# LCs.net
KiCad netlist of a schematic drawn in Altium Designer
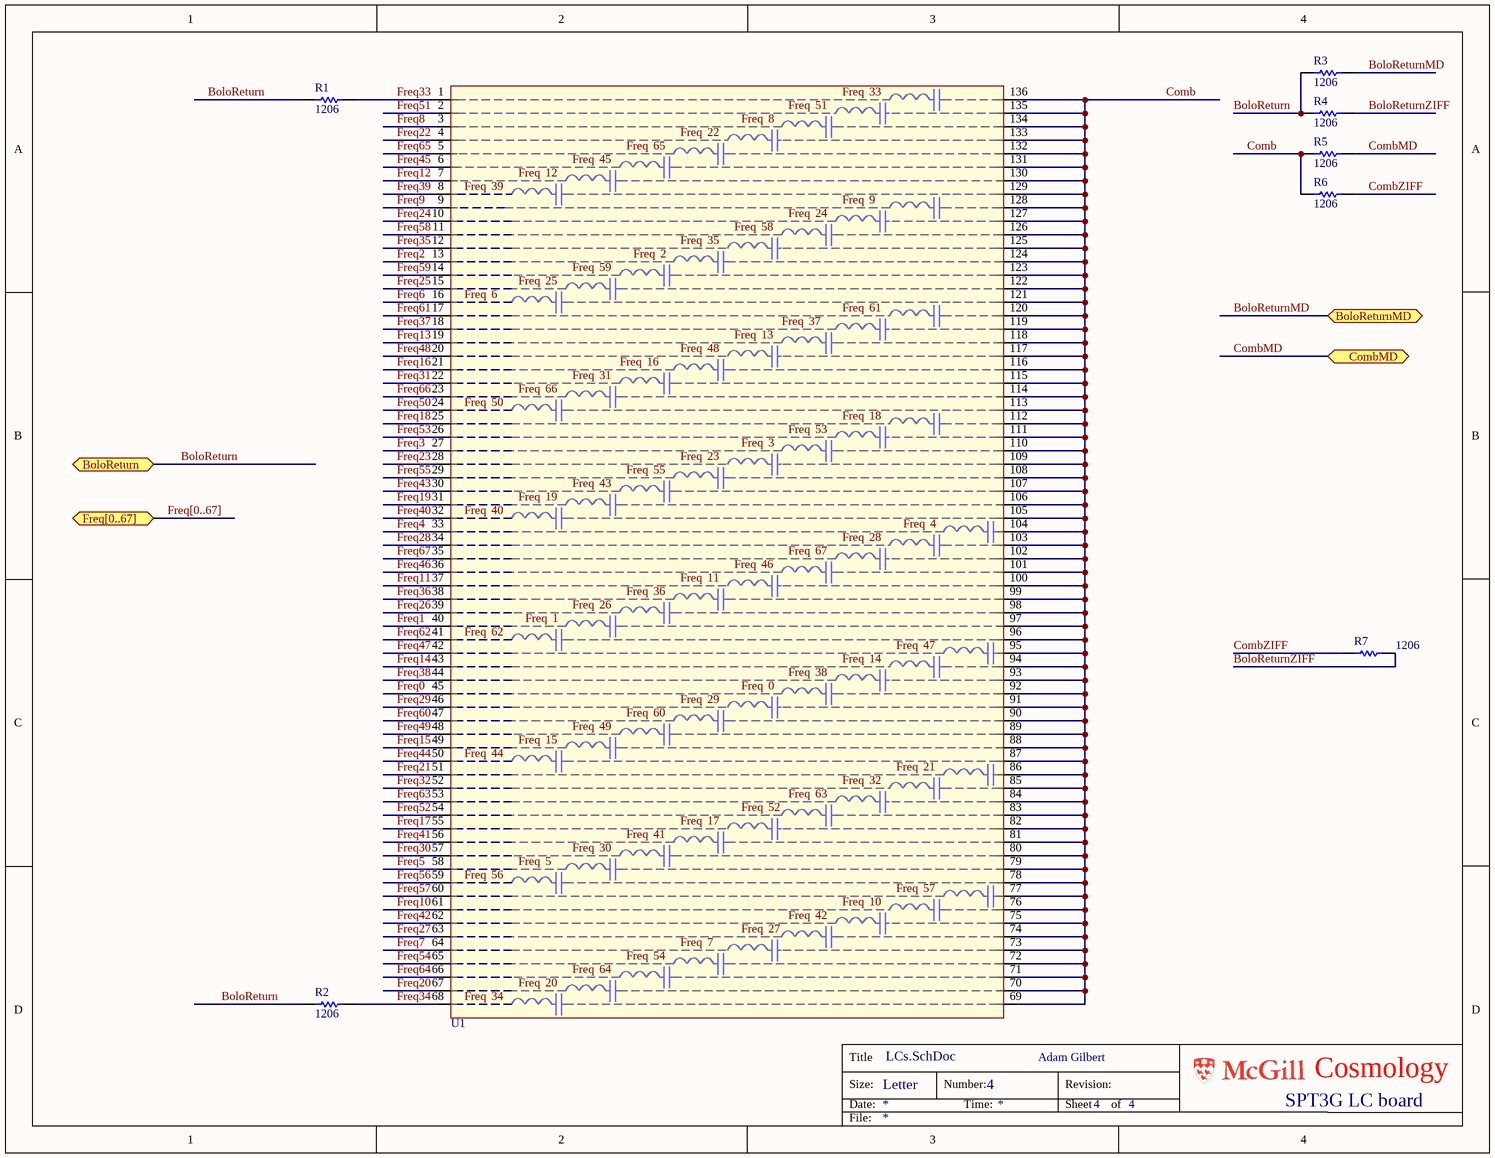
[diagram p0: LCs.SchDoc]

(export (version "E")
  (design (tool "Eeschema 10.0.6"))
  (components
    (comp (ref "R1")
      (value "Res1206")
      (footprint "1206")
      (description "Resistor")
      (libsource (lib "SPT3G_LCBoard") (part "Res1206"))
    )
    (comp (ref "R2")
      (value "Res1206")
      (footprint "1206")
      (description "Resistor")
      (libsource (lib "SPT3G_LCBoard") (part "Res1206"))
    )
    (comp (ref "R3")
      (value "Res1206")
      (footprint "1206")
      (description "Resistor")
      (libsource (lib "SPT3G_LCBoard") (part "Res1206"))
    )
    (comp (ref "R4")
      (value "Res1206")
      (footprint "1206")
      (description "Resistor")
      (libsource (lib "SPT3G_LCBoard") (part "Res1206"))
    )
    (comp (ref "R5")
      (value "Res1206")
      (footprint "1206")
      (description "Resistor")
      (libsource (lib "SPT3G_LCBoard") (part "Res1206"))
    )
    (comp (ref "R6")
      (value "Res1206")
      (footprint "1206")
      (description "Resistor")
      (libsource (lib "SPT3G_LCBoard") (part "Res1206"))
    )
    (comp (ref "R7")
      (value "Res1206")
      (footprint "1206")
      (description "Resistor")
      (libsource (lib "SPT3G_LCBoard") (part "Res1206"))
    )
    (comp (ref "U1")
      (value "LC68_wafer")
      (footprint "68xLC")
      (description "Gold bonded integrated LC")
      (libsource (lib "SPT3G_LCBoard") (part "LC68Wafer"))
    )
  )
  (nets
    (net (code "1") (name "/BoloReturn") (class "Default")
      (node (ref "R1") (pin "1") (pinfunction "1_1") (pintype "passive"))
      (node (ref "R2") (pin "1") (pinfunction "1_1") (pintype "passive"))
      (node (ref "R3") (pin "1") (pinfunction "1_1") (pintype "passive"))
      (node (ref "R4") (pin "1") (pinfunction "1_1") (pintype "passive"))
    )
    (net (code "2") (name "/BoloReturnMD") (class "Default")
      (node (ref "R3") (pin "2") (pinfunction "2_2") (pintype "passive"))
    )
    (net (code "3") (name "/BoloReturnZIFF") (class "Default")
      (node (ref "R4") (pin "2") (pinfunction "2_2") (pintype "passive"))
      (node (ref "R7") (pin "1") (pinfunction "1_1") (pintype "passive"))
    )
    (net (code "4") (name "/Comb") (class "Default")
      (node (ref "R5") (pin "1") (pinfunction "1_1") (pintype "passive"))
      (node (ref "R6") (pin "1") (pinfunction "1_1") (pintype "passive"))
      (node (ref "U1") (pin "100") (pinfunction "100_100") (pintype "passive"))
      (node (ref "U1") (pin "101") (pinfunction "101_101") (pintype "passive"))
      (node (ref "U1") (pin "102") (pinfunction "102_102") (pintype "passive"))
      (node (ref "U1") (pin "103") (pinfunction "103_103") (pintype "passive"))
      (node (ref "U1") (pin "104") (pinfunction "104_104") (pintype "passive"))
      (node (ref "U1") (pin "105") (pinfunction "105_105") (pintype "passive"))
      (node (ref "U1") (pin "106") (pinfunction "106_106") (pintype "passive"))
      (node (ref "U1") (pin "107") (pinfunction "107_107") (pintype "passive"))
      (node (ref "U1") (pin "108") (pinfunction "108_108") (pintype "passive"))
      (node (ref "U1") (pin "109") (pinfunction "109_109") (pintype "passive"))
      (node (ref "U1") (pin "110") (pinfunction "110_110") (pintype "passive"))
      (node (ref "U1") (pin "111") (pinfunction "111_111") (pintype "passive"))
      (node (ref "U1") (pin "112") (pinfunction "112_112") (pintype "passive"))
      (node (ref "U1") (pin "113") (pinfunction "113_113") (pintype "passive"))
      (node (ref "U1") (pin "114") (pinfunction "114_114") (pintype "passive"))
      (node (ref "U1") (pin "115") (pinfunction "115_115") (pintype "passive"))
      (node (ref "U1") (pin "116") (pinfunction "116_116") (pintype "passive"))
      (node (ref "U1") (pin "117") (pinfunction "117_117") (pintype "passive"))
      (node (ref "U1") (pin "118") (pinfunction "118_118") (pintype "passive"))
      (node (ref "U1") (pin "119") (pinfunction "119_119") (pintype "passive"))
      (node (ref "U1") (pin "120") (pinfunction "120_120") (pintype "passive"))
      (node (ref "U1") (pin "121") (pinfunction "121_121") (pintype "passive"))
      (node (ref "U1") (pin "122") (pinfunction "122_122") (pintype "passive"))
      (node (ref "U1") (pin "123") (pinfunction "123_123") (pintype "passive"))
      (node (ref "U1") (pin "124") (pinfunction "124_124") (pintype "passive"))
      (node (ref "U1") (pin "125") (pinfunction "125_125") (pintype "passive"))
      (node (ref "U1") (pin "126") (pinfunction "126_126") (pintype "passive"))
      (node (ref "U1") (pin "127") (pinfunction "127_127") (pintype "passive"))
      (node (ref "U1") (pin "128") (pinfunction "128_128") (pintype "passive"))
      (node (ref "U1") (pin "129") (pinfunction "129_129") (pintype "passive"))
      (node (ref "U1") (pin "130") (pinfunction "130_130") (pintype "passive"))
      (node (ref "U1") (pin "131") (pinfunction "131_131") (pintype "passive"))
      (node (ref "U1") (pin "132") (pinfunction "132_132") (pintype "passive"))
      (node (ref "U1") (pin "133") (pinfunction "133_133") (pintype "passive"))
      (node (ref "U1") (pin "134") (pinfunction "134_134") (pintype "passive"))
      (node (ref "U1") (pin "135") (pinfunction "135_135") (pintype "passive"))
      (node (ref "U1") (pin "136") (pinfunction "136_136") (pintype "passive"))
      (node (ref "U1") (pin "69") (pinfunction "69_69") (pintype "passive"))
      (node (ref "U1") (pin "70") (pinfunction "70_70") (pintype "passive"))
      (node (ref "U1") (pin "71") (pinfunction "71_71") (pintype "passive"))
      (node (ref "U1") (pin "72") (pinfunction "72_72") (pintype "passive"))
      (node (ref "U1") (pin "73") (pinfunction "73_73") (pintype "passive"))
      (node (ref "U1") (pin "74") (pinfunction "74_74") (pintype "passive"))
      (node (ref "U1") (pin "75") (pinfunction "75_75") (pintype "passive"))
      (node (ref "U1") (pin "76") (pinfunction "76_76") (pintype "passive"))
      (node (ref "U1") (pin "77") (pinfunction "77_77") (pintype "passive"))
      (node (ref "U1") (pin "78") (pinfunction "78_78") (pintype "passive"))
      (node (ref "U1") (pin "79") (pinfunction "79_79") (pintype "passive"))
      (node (ref "U1") (pin "80") (pinfunction "80_80") (pintype "passive"))
      (node (ref "U1") (pin "81") (pinfunction "81_81") (pintype "passive"))
      (node (ref "U1") (pin "82") (pinfunction "82_82") (pintype "passive"))
      (node (ref "U1") (pin "83") (pinfunction "83_83") (pintype "passive"))
      (node (ref "U1") (pin "84") (pinfunction "84_84") (pintype "passive"))
      (node (ref "U1") (pin "85") (pinfunction "85_85") (pintype "passive"))
      (node (ref "U1") (pin "86") (pinfunction "86_86") (pintype "passive"))
      (node (ref "U1") (pin "87") (pinfunction "87_87") (pintype "passive"))
      (node (ref "U1") (pin "88") (pinfunction "88_88") (pintype "passive"))
      (node (ref "U1") (pin "89") (pinfunction "89_89") (pintype "passive"))
      (node (ref "U1") (pin "90") (pinfunction "90_90") (pintype "passive"))
      (node (ref "U1") (pin "91") (pinfunction "91_91") (pintype "passive"))
      (node (ref "U1") (pin "92") (pinfunction "92_92") (pintype "passive"))
      (node (ref "U1") (pin "93") (pinfunction "93_93") (pintype "passive"))
      (node (ref "U1") (pin "94") (pinfunction "94_94") (pintype "passive"))
      (node (ref "U1") (pin "95") (pinfunction "95_95") (pintype "passive"))
      (node (ref "U1") (pin "96") (pinfunction "96_96") (pintype "passive"))
      (node (ref "U1") (pin "97") (pinfunction "97_97") (pintype "passive"))
      (node (ref "U1") (pin "98") (pinfunction "98_98") (pintype "passive"))
      (node (ref "U1") (pin "99") (pinfunction "99_99") (pintype "passive"))
    )
    (net (code "5") (name "/CombMD") (class "Default")
      (node (ref "R5") (pin "2") (pinfunction "2_2") (pintype "passive"))
    )
    (net (code "6") (name "/CombZIFF") (class "Default")
      (node (ref "R6") (pin "2") (pinfunction "2_2") (pintype "passive"))
      (node (ref "R7") (pin "2") (pinfunction "2_2") (pintype "passive"))
    )
    (net (code "7") (name "/Freq0") (class "Default")
      (node (ref "U1") (pin "45") (pinfunction "45_45") (pintype "passive"))
    )
    (net (code "8") (name "/Freq1") (class "Default")
      (node (ref "U1") (pin "40") (pinfunction "40_40") (pintype "passive"))
    )
    (net (code "9") (name "/Freq2") (class "Default")
      (node (ref "U1") (pin "13") (pinfunction "13_13") (pintype "passive"))
    )
    (net (code "10") (name "/Freq3") (class "Default")
      (node (ref "U1") (pin "27") (pinfunction "27_27") (pintype "passive"))
    )
    (net (code "11") (name "/Freq4") (class "Default")
      (node (ref "U1") (pin "33") (pinfunction "33_33") (pintype "passive"))
    )
    (net (code "12") (name "/Freq5") (class "Default")
      (node (ref "U1") (pin "58") (pinfunction "58_58") (pintype "passive"))
    )
    (net (code "13") (name "/Freq6") (class "Default")
      (node (ref "U1") (pin "16") (pinfunction "16_16") (pintype "passive"))
    )
    (net (code "14") (name "/Freq7") (class "Default")
      (node (ref "U1") (pin "64") (pinfunction "64_64") (pintype "passive"))
    )
    (net (code "15") (name "/Freq8") (class "Default")
      (node (ref "U1") (pin "3") (pinfunction "3_3") (pintype "passive"))
    )
    (net (code "16") (name "/Freq9") (class "Default")
      (node (ref "U1") (pin "9") (pinfunction "9_9") (pintype "passive"))
    )
    (net (code "17") (name "/Freq10") (class "Default")
      (node (ref "U1") (pin "61") (pinfunction "61_61") (pintype "passive"))
    )
    (net (code "18") (name "/Freq11") (class "Default")
      (node (ref "U1") (pin "37") (pinfunction "37_37") (pintype "passive"))
    )
    (net (code "19") (name "/Freq12") (class "Default")
      (node (ref "U1") (pin "7") (pinfunction "7_7") (pintype "passive"))
    )
    (net (code "20") (name "/Freq13") (class "Default")
      (node (ref "U1") (pin "19") (pinfunction "19_19") (pintype "passive"))
    )
    (net (code "21") (name "/Freq14") (class "Default")
      (node (ref "U1") (pin "43") (pinfunction "43_43") (pintype "passive"))
    )
    (net (code "22") (name "/Freq15") (class "Default")
      (node (ref "U1") (pin "49") (pinfunction "49_49") (pintype "passive"))
    )
    (net (code "23") (name "/Freq16") (class "Default")
      (node (ref "U1") (pin "21") (pinfunction "21_21") (pintype "passive"))
    )
    (net (code "24") (name "/Freq17") (class "Default")
      (node (ref "U1") (pin "55") (pinfunction "55_55") (pintype "passive"))
    )
    (net (code "25") (name "/Freq18") (class "Default")
      (node (ref "U1") (pin "25") (pinfunction "25_25") (pintype "passive"))
    )
    (net (code "26") (name "/Freq19") (class "Default")
      (node (ref "U1") (pin "31") (pinfunction "31_31") (pintype "passive"))
    )
    (net (code "27") (name "/Freq20") (class "Default")
      (node (ref "U1") (pin "67") (pinfunction "67_67") (pintype "passive"))
    )
    (net (code "28") (name "/Freq21") (class "Default")
      (node (ref "U1") (pin "51") (pinfunction "51_51") (pintype "passive"))
    )
    (net (code "29") (name "/Freq22") (class "Default")
      (node (ref "U1") (pin "4") (pinfunction "4_4") (pintype "passive"))
    )
    (net (code "30") (name "/Freq23") (class "Default")
      (node (ref "U1") (pin "28") (pinfunction "28_28") (pintype "passive"))
    )
    (net (code "31") (name "/Freq24") (class "Default")
      (node (ref "U1") (pin "10") (pinfunction "10_10") (pintype "passive"))
    )
    (net (code "32") (name "/Freq25") (class "Default")
      (node (ref "U1") (pin "15") (pinfunction "15_15") (pintype "passive"))
    )
    (net (code "33") (name "/Freq26") (class "Default")
      (node (ref "U1") (pin "39") (pinfunction "39_39") (pintype "passive"))
    )
    (net (code "34") (name "/Freq27") (class "Default")
      (node (ref "U1") (pin "63") (pinfunction "63_63") (pintype "passive"))
    )
    (net (code "35") (name "/Freq28") (class "Default")
      (node (ref "U1") (pin "34") (pinfunction "34_34") (pintype "passive"))
    )
    (net (code "36") (name "/Freq29") (class "Default")
      (node (ref "U1") (pin "46") (pinfunction "46_46") (pintype "passive"))
    )
    (net (code "37") (name "/Freq30") (class "Default")
      (node (ref "U1") (pin "57") (pinfunction "57_57") (pintype "passive"))
    )
    (net (code "38") (name "/Freq31") (class "Default")
      (node (ref "U1") (pin "22") (pinfunction "22_22") (pintype "passive"))
    )
    (net (code "39") (name "/Freq32") (class "Default")
      (node (ref "U1") (pin "52") (pinfunction "52_52") (pintype "passive"))
    )
    (net (code "40") (name "/Freq33") (class "Default")
      (node (ref "R1") (pin "2") (pinfunction "2_2") (pintype "passive"))
      (node (ref "U1") (pin "1") (pinfunction "1_1") (pintype "passive"))
    )
    (net (code "41") (name "/Freq34") (class "Default")
      (node (ref "R2") (pin "2") (pinfunction "2_2") (pintype "passive"))
      (node (ref "U1") (pin "68") (pinfunction "68_68") (pintype "passive"))
    )
    (net (code "42") (name "/Freq35") (class "Default")
      (node (ref "U1") (pin "12") (pinfunction "12_12") (pintype "passive"))
    )
    (net (code "43") (name "/Freq36") (class "Default")
      (node (ref "U1") (pin "38") (pinfunction "38_38") (pintype "passive"))
    )
    (net (code "44") (name "/Freq37") (class "Default")
      (node (ref "U1") (pin "18") (pinfunction "18_18") (pintype "passive"))
    )
    (net (code "45") (name "/Freq38") (class "Default")
      (node (ref "U1") (pin "44") (pinfunction "44_44") (pintype "passive"))
    )
    (net (code "46") (name "/Freq39") (class "Default")
      (node (ref "U1") (pin "8") (pinfunction "8_8") (pintype "passive"))
    )
    (net (code "47") (name "/Freq40") (class "Default")
      (node (ref "U1") (pin "32") (pinfunction "32_32") (pintype "passive"))
    )
    (net (code "48") (name "/Freq41") (class "Default")
      (node (ref "U1") (pin "56") (pinfunction "56_56") (pintype "passive"))
    )
    (net (code "49") (name "/Freq42") (class "Default")
      (node (ref "U1") (pin "62") (pinfunction "62_62") (pintype "passive"))
    )
    (net (code "50") (name "/Freq43") (class "Default")
      (node (ref "U1") (pin "30") (pinfunction "30_30") (pintype "passive"))
    )
    (net (code "51") (name "/Freq44") (class "Default")
      (node (ref "U1") (pin "50") (pinfunction "50_50") (pintype "passive"))
    )
    (net (code "52") (name "/Freq45") (class "Default")
      (node (ref "U1") (pin "6") (pinfunction "6_6") (pintype "passive"))
    )
    (net (code "53") (name "/Freq46") (class "Default")
      (node (ref "U1") (pin "36") (pinfunction "36_36") (pintype "passive"))
    )
    (net (code "54") (name "/Freq47") (class "Default")
      (node (ref "U1") (pin "42") (pinfunction "42_42") (pintype "passive"))
    )
    (net (code "55") (name "/Freq48") (class "Default")
      (node (ref "U1") (pin "20") (pinfunction "20_20") (pintype "passive"))
    )
    (net (code "56") (name "/Freq49") (class "Default")
      (node (ref "U1") (pin "48") (pinfunction "48_48") (pintype "passive"))
    )
    (net (code "57") (name "/Freq50") (class "Default")
      (node (ref "U1") (pin "24") (pinfunction "24_24") (pintype "passive"))
    )
    (net (code "58") (name "/Freq51") (class "Default")
      (node (ref "U1") (pin "2") (pinfunction "2_2") (pintype "passive"))
    )
    (net (code "59") (name "/Freq52") (class "Default")
      (node (ref "U1") (pin "54") (pinfunction "54_54") (pintype "passive"))
    )
    (net (code "60") (name "/Freq53") (class "Default")
      (node (ref "U1") (pin "26") (pinfunction "26_26") (pintype "passive"))
    )
    (net (code "61") (name "/Freq54") (class "Default")
      (node (ref "U1") (pin "65") (pinfunction "65_65") (pintype "passive"))
    )
    (net (code "62") (name "/Freq55") (class "Default")
      (node (ref "U1") (pin "29") (pinfunction "29_29") (pintype "passive"))
    )
    (net (code "63") (name "/Freq56") (class "Default")
      (node (ref "U1") (pin "59") (pinfunction "59_59") (pintype "passive"))
    )
    (net (code "64") (name "/Freq57") (class "Default")
      (node (ref "U1") (pin "60") (pinfunction "60_60") (pintype "passive"))
    )
    (net (code "65") (name "/Freq58") (class "Default")
      (node (ref "U1") (pin "11") (pinfunction "11_11") (pintype "passive"))
    )
    (net (code "66") (name "/Freq59") (class "Default")
      (node (ref "U1") (pin "14") (pinfunction "14_14") (pintype "passive"))
    )
    (net (code "67") (name "/Freq60") (class "Default")
      (node (ref "U1") (pin "47") (pinfunction "47_47") (pintype "passive"))
    )
    (net (code "68") (name "/Freq61") (class "Default")
      (node (ref "U1") (pin "17") (pinfunction "17_17") (pintype "passive"))
    )
    (net (code "69") (name "/Freq62") (class "Default")
      (node (ref "U1") (pin "41") (pinfunction "41_41") (pintype "passive"))
    )
    (net (code "70") (name "/Freq63") (class "Default")
      (node (ref "U1") (pin "53") (pinfunction "53_53") (pintype "passive"))
    )
    (net (code "71") (name "/Freq64") (class "Default")
      (node (ref "U1") (pin "66") (pinfunction "66_66") (pintype "passive"))
    )
    (net (code "72") (name "/Freq65") (class "Default")
      (node (ref "U1") (pin "5") (pinfunction "5_5") (pintype "passive"))
    )
    (net (code "73") (name "/Freq66") (class "Default")
      (node (ref "U1") (pin "23") (pinfunction "23_23") (pintype "passive"))
    )
    (net (code "74") (name "/Freq67") (class "Default")
      (node (ref "U1") (pin "35") (pinfunction "35_35") (pintype "passive"))
    )
  )
)
